# mlx-brd1_091-sensor.net
KiCad netlist of a schematic drawn in Altium Designer
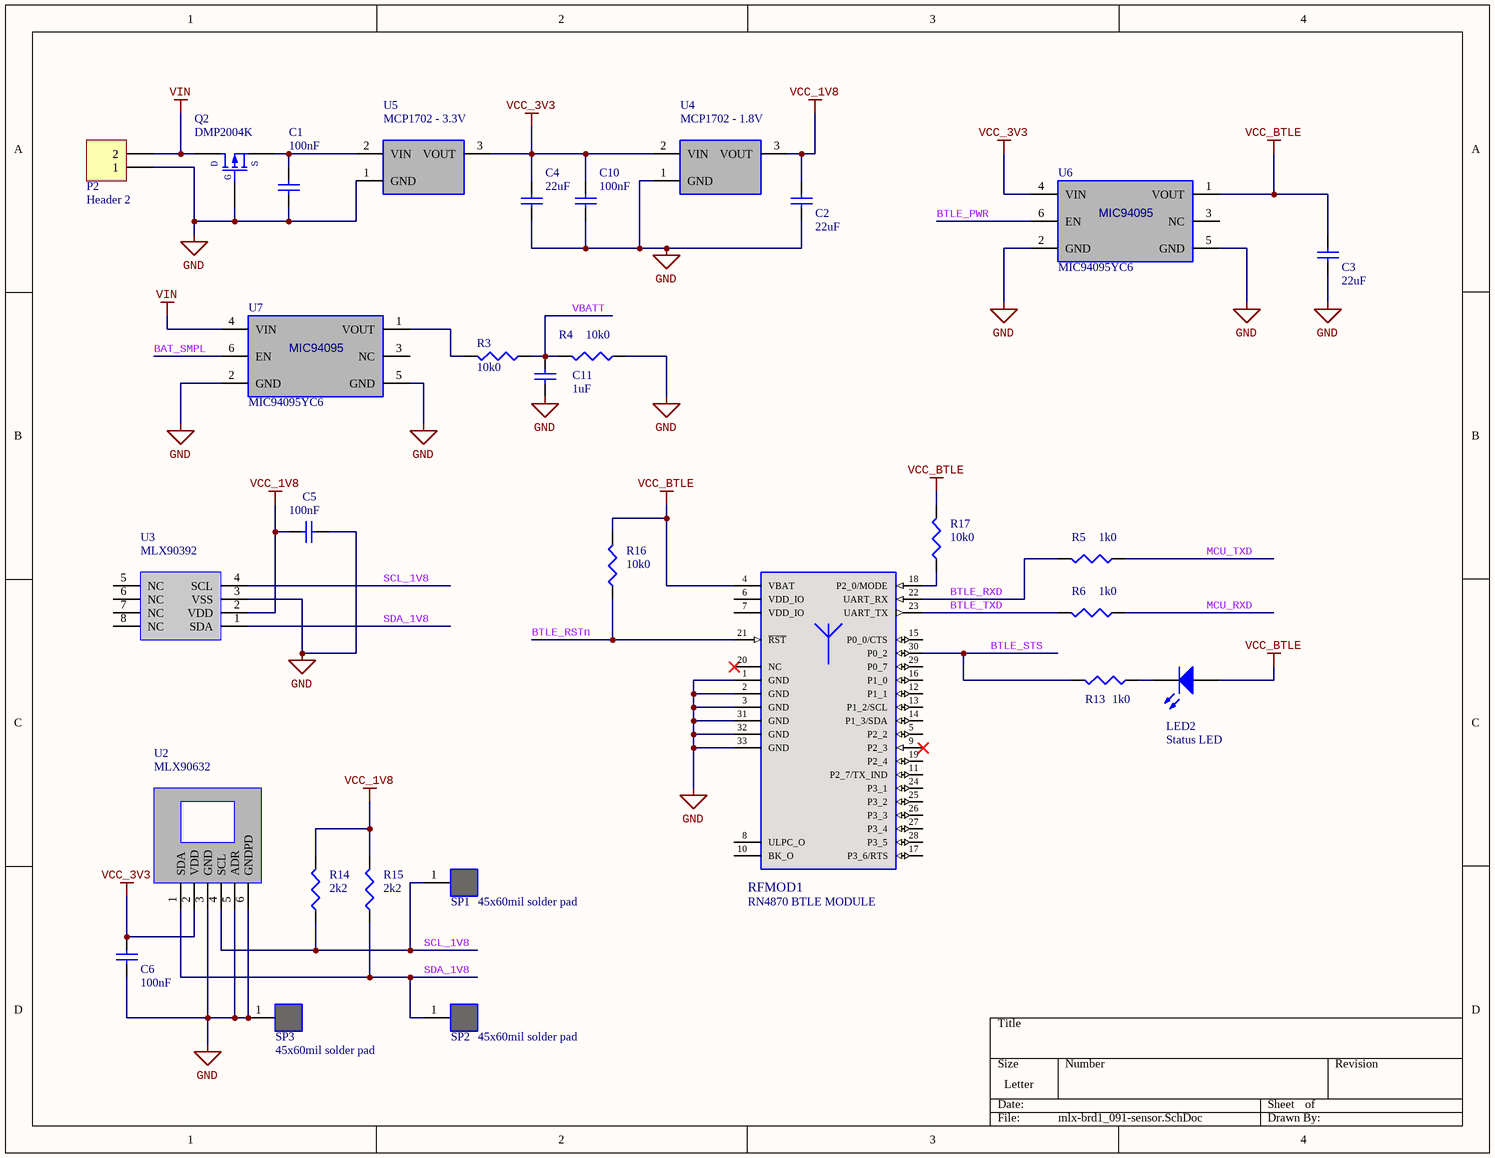
[diagram p0: mlx-brd1_091-sensor.SchDoc]

(export (version "E")
  (design (tool "Eeschema 10.0.6"))
  (components
    (comp (ref "C1")
      (value "100nF")
      (footprint "CAPC1608N")
      (description "Capacitor")
      (fields (field (name "MANUFACTURER") "Yageo") (field (name "MPN") "CC0603KPX7R9BB104"))
      (libsource (lib "Miscellaneous Devices") (part "Cap"))
    )
    (comp (ref "C2")
      (value "22uF")
      (footprint "CAPC3216N")
      (description "Capacitor")
      (fields (field (name "MANUFACTURER") "Yageo") (field (name "MPN") "CC1206MKX5R6BB226"))
      (libsource (lib "Miscellaneous Devices") (part "Cap"))
    )
    (comp (ref "C3")
      (value "22uF")
      (footprint "CAPC3216N")
      (description "Capacitor")
      (fields (field (name "MANUFACTURER") "Yageo") (field (name "MPN") "CC1206MKX5R6BB226"))
      (libsource (lib "Miscellaneous Devices") (part "Cap"))
    )
    (comp (ref "C4")
      (value "22uF")
      (footprint "CAPC3216N")
      (description "Capacitor")
      (fields (field (name "MANUFACTURER") "Yageo") (field (name "MPN") "CC1206MKX5R6BB226"))
      (libsource (lib "Miscellaneous Devices") (part "Cap"))
    )
    (comp (ref "C5")
      (value "100nF")
      (footprint "CAPC1608N")
      (description "Capacitor")
      (fields (field (name "MANUFACTURER") "Yageo") (field (name "MPN") "CC0603KPX7R9BB104"))
      (libsource (lib "Miscellaneous Devices") (part "Cap"))
    )
    (comp (ref "C6")
      (value "100nF")
      (footprint "CAPC1608N")
      (description "Capacitor")
      (fields (field (name "MANUFACTURER") "Yageo") (field (name "MPN") "CC0603KPX7R9BB104"))
      (libsource (lib "Miscellaneous Devices") (part "Cap"))
    )
    (comp (ref "C10")
      (value "100nF")
      (footprint "CAPC1608N")
      (description "Capacitor")
      (fields (field (name "MANUFACTURER") "Yageo") (field (name "MPN") "CC0603KPX7R9BB104"))
      (libsource (lib "Miscellaneous Devices") (part "Cap"))
    )
    (comp (ref "C11")
      (value "1uF")
      (footprint "CAPC1608N")
      (description "Capacitor")
      (fields (field (name "MANUFACTURER") "Taiyo Yuden") (field (name "MPN") "LMK107B7105KA-T"))
      (libsource (lib "Miscellaneous Devices") (part "Cap"))
    )
    (comp (ref "LED2")
      (value "Status LED")
      (footprint "3.2X1.6X1.1")
      (description "Typical RED GaAs LED")
      (fields (field (name "MANUFACTURER") "Inolux") (field (name "MPN") "IN-S126ATA"))
      (libsource (lib "Miscellaneous Devices") (part "LED1"))
    )
    (comp (ref "P2")
      (value "Header 2")
      (footprint "HDR1X2")
      (description "Header, 2-Pin")
      (fields (field (name "MANUFACTURER") "n/a"))
      (libsource (lib "Miscellaneous Connectors") (part "Header 2"))
    )
    (comp (ref "Q2")
      (value "DMP2004K")
      (footprint "SOT23-3N")
      (description "P-Channel MOSFET")
      (fields (field (name "MANUFACTURER") "Diodes Incorporated") (field (name "MPN") "DMP2004K-7"))
      (libsource (lib "melexis_demo") (part "DMP2004K"))
    )
    (comp (ref "R3")
      (value "10k0")
      (footprint "RESC1608N")
      (description "Resistor")
      (fields (field (name "MANUFACTURER") "Stackpole Electronics Inc") (field (name "MPN") "CF18JT10K0"))
      (libsource (lib "Miscellaneous Devices") (part "Res3"))
    )
    (comp (ref "R4")
      (value "10k0")
      (footprint "RESC1608N")
      (description "Resistor")
      (fields (field (name "MANUFACTURER") "Stackpole Electronics Inc") (field (name "MPN") "CF18JT10K0"))
      (libsource (lib "Miscellaneous Devices") (part "Res3"))
    )
    (comp (ref "R5")
      (value "1k0")
      (footprint "RESC1608N")
      (description "Resistor")
      (fields (field (name "MANUFACTURER") "Stackpole Electronics Inc") (field (name "MPN") "CF18JT10K0"))
      (libsource (lib "Miscellaneous Devices") (part "Res3"))
    )
    (comp (ref "R6")
      (value "1k0")
      (footprint "RESC1608N")
      (description "Resistor")
      (fields (field (name "MANUFACTURER") "Stackpole Electronics Inc") (field (name "MPN") "CF18JT10K0"))
      (libsource (lib "Miscellaneous Devices") (part "Res3"))
    )
    (comp (ref "R13")
      (value "1k0")
      (footprint "RESC1608N")
      (description "Resistor")
      (fields (field (name "MANUFACTURER") "Stackpole Electronics Inc") (field (name "MPN") "CF18JT10K0"))
      (libsource (lib "Miscellaneous Devices") (part "Res3"))
    )
    (comp (ref "R14")
      (value "2k2")
      (footprint "RESC1608N")
      (description "Resistor")
      (fields (field (name "MANUFACTURER") "Stackpole Electronics Inc") (field (name "MPN") "CF18JT10K0"))
      (libsource (lib "Miscellaneous Devices") (part "Res3"))
    )
    (comp (ref "R15")
      (value "2k2")
      (footprint "RESC1608N")
      (description "Resistor")
      (fields (field (name "MANUFACTURER") "Stackpole Electronics Inc") (field (name "MPN") "CF18JT10K0"))
      (libsource (lib "Miscellaneous Devices") (part "Res3"))
    )
    (comp (ref "R16")
      (value "10k0")
      (footprint "RESC1608N")
      (description "Resistor")
      (fields (field (name "MANUFACTURER") "Stackpole Electronics Inc") (field (name "MPN") "CF18JT10K0"))
      (libsource (lib "Miscellaneous Devices") (part "Res3"))
    )
    (comp (ref "R17")
      (value "10k0")
      (footprint "RESC1608N")
      (description "Resistor")
      (fields (field (name "MANUFACTURER") "Stackpole Electronics Inc") (field (name "MPN") "CF18JT10K0"))
      (libsource (lib "Miscellaneous Devices") (part "Res3"))
    )
    (comp (ref "RFMOD1")
      (value "RN4870 BTLE MODULE")
      (footprint "AP6-00539")
      (description "Bluetooth LE Module")
      (fields (field (name "MANUFACTURER") "Microchip Technology") (field (name "MPN") "RN4870-V/RM140"))
      (libsource (lib "melexis_demo") (part "RN4870-V"))
    )
    (comp (ref "SP1")
      (value "45x60mil solder pad")
      (footprint "sp45x60")
      (libsource (lib "mlx-brd1") (part "sp45x60"))
    )
    (comp (ref "SP2")
      (value "45x60mil solder pad")
      (footprint "sp45x60")
      (libsource (lib "mlx-brd1") (part "sp45x60"))
    )
    (comp (ref "SP3")
      (value "45x60mil solder pad")
      (footprint "sp45x60")
      (libsource (lib "mlx-brd1") (part "sp45x60"))
    )
    (comp (ref "U2")
      (value "MLX90632")
      (footprint "MLX90632_FIR_M2")
      (fields (field (name "MANUFACTURER") "Melexis") (field (name "MPN") "MLX90632-S-LD-DCB-100"))
      (libsource (lib "melexis_demo") (part "MLX90632-FIR"))
    )
    (comp (ref "U3")
      (value "MLX90392")
      (footprint "UTDFN8_2.5x2x0.4V2")
      (fields (field (name "MANUFACTURER") "Melexis") (field (name "MPN") "MLX90392ELQ-AAA-010-RE"))
      (libsource (lib "melexis_demo") (part "MLX90392-mag"))
    )
    (comp (ref "U4")
      (value "MCP1702 - 1.8V")
      (footprint "MC1702-TO92")
      (fields (field (name "MANUFACTURER") "Microchip Technology") (field (name "MPN") "MCP1702-3302E/TO"))
      (libsource (lib "melexis_demo") (part "MCP1702-TO92"))
    )
    (comp (ref "U5")
      (value "MCP1702 - 3.3V")
      (footprint "MC1702-TO92")
      (fields (field (name "MANUFACTURER") "Microchip Technology") (field (name "MPN") "MCP1702-1802E/TO"))
      (libsource (lib "melexis_demo") (part "MCP1702-TO92"))
    )
    (comp (ref "U6")
      (value "MIC94095YC6")
      (footprint "SC-70")
      (fields (field (name "MANUFACTURER") "Microchip Technology") (field (name "MPN") "MIC94095YC6-TR"))
      (libsource (lib "mlx-brd1") (part "MIC94095YC6"))
    )
    (comp (ref "U7")
      (value "MIC94095YC6")
      (footprint "SC-70")
      (fields (field (name "MANUFACTURER") "Microchip Technology") (field (name "MPN") "MIC94095YC6-TR"))
      (libsource (lib "mlx-brd1") (part "MIC94095YC6"))
    )
  )
  (nets
    (net (code "1") (name "/BAT_SMPL") (class "Default")
      (node (ref "U7") (pin "6") (pinfunction "EN_6") (pintype "passive"))
    )
    (net (code "2") (name "/BTLE_PWR") (class "Default")
      (node (ref "U6") (pin "6") (pinfunction "EN_6") (pintype "passive"))
    )
    (net (code "3") (name "/BTLE_RSTn") (class "Default")
      (node (ref "R16") (pin "1") (pinfunction "1_1") (pintype "passive"))
      (node (ref "RFMOD1") (pin "21") (pinfunction "~{RST}_21") (pintype "input"))
    )
    (net (code "4") (name "/BTLE_RXD") (class "Default")
      (node (ref "R5") (pin "2") (pinfunction "2_2") (pintype "passive"))
      (node (ref "RFMOD1") (pin "22") (pinfunction "UART_RX_22") (pintype "input"))
    )
    (net (code "5") (name "/BTLE_STS") (class "Default")
      (node (ref "R13") (pin "2") (pinfunction "2_2") (pintype "passive"))
      (node (ref "RFMOD1") (pin "30") (pinfunction "P0_2_30") (pintype "bidirectional"))
    )
    (net (code "6") (name "/BTLE_TXD") (class "Default")
      (node (ref "R6") (pin "2") (pinfunction "2_2") (pintype "passive"))
      (node (ref "RFMOD1") (pin "23") (pinfunction "UART_TX_23") (pintype "output"))
    )
    (net (code "7") (name "/MCU_RXD") (class "Default")
      (node (ref "R6") (pin "1") (pinfunction "1_1") (pintype "passive"))
    )
    (net (code "8") (name "/MCU_TXD") (class "Default")
      (node (ref "R5") (pin "1") (pinfunction "1_1") (pintype "passive"))
    )
    (net (code "9") (name "/SCL_1V8") (class "Default")
      (node (ref "R14") (pin "1") (pinfunction "1_1") (pintype "passive"))
      (node (ref "SP1") (pin "1") (pinfunction "1_1") (pintype "passive"))
      (node (ref "U2") (pin "4") (pinfunction "SCL_4") (pintype "passive"))
      (node (ref "U3") (pin "4") (pinfunction "SCL_4") (pintype "passive"))
    )
    (net (code "10") (name "/SDA_1V8") (class "Default")
      (node (ref "R15") (pin "1") (pinfunction "1_1") (pintype "passive"))
      (node (ref "SP2") (pin "1") (pinfunction "1_1") (pintype "passive"))
      (node (ref "U2") (pin "1") (pinfunction "SDA_1") (pintype "passive"))
      (node (ref "U3") (pin "1") (pinfunction "SDA_1") (pintype "passive"))
    )
    (net (code "11") (name "/VBATT") (class "Default")
      (node (ref "C11") (pin "2") (pinfunction "2_2") (pintype "passive"))
      (node (ref "R3") (pin "1") (pinfunction "1_1") (pintype "passive"))
      (node (ref "R4") (pin "2") (pinfunction "2_2") (pintype "passive"))
    )
    (net (code "12") (name "GND") (class "Default")
      (node (ref "C1") (pin "1") (pinfunction "1_1") (pintype "passive"))
      (node (ref "C10") (pin "1") (pinfunction "1_1") (pintype "passive"))
      (node (ref "C11") (pin "1") (pinfunction "1_1") (pintype "passive"))
      (node (ref "C2") (pin "1") (pinfunction "1_1") (pintype "passive"))
      (node (ref "C3") (pin "1") (pinfunction "1_1") (pintype "passive"))
      (node (ref "C4") (pin "1") (pinfunction "1_1") (pintype "passive"))
      (node (ref "C5") (pin "1") (pinfunction "1_1") (pintype "passive"))
      (node (ref "C6") (pin "1") (pinfunction "1_1") (pintype "passive"))
      (node (ref "P2") (pin "1") (pinfunction "1_1") (pintype "passive"))
      (node (ref "Q2") (pin "1") (pinfunction "G_1") (pintype "passive"))
      (node (ref "R4") (pin "1") (pinfunction "1_1") (pintype "passive"))
      (node (ref "RFMOD1") (pin "1") (pinfunction "GND_1") (pintype "power_in"))
      (node (ref "RFMOD1") (pin "2") (pinfunction "GND_2") (pintype "power_in"))
      (node (ref "RFMOD1") (pin "3") (pinfunction "GND_3") (pintype "power_in"))
      (node (ref "RFMOD1") (pin "31") (pinfunction "GND_31") (pintype "power_in"))
      (node (ref "RFMOD1") (pin "32") (pinfunction "GND_32") (pintype "power_in"))
      (node (ref "RFMOD1") (pin "33") (pinfunction "GND_33") (pintype "power_in"))
      (node (ref "SP3") (pin "1") (pinfunction "1_1") (pintype "passive"))
      (node (ref "U2") (pin "3") (pinfunction "GND_3") (pintype "passive"))
      (node (ref "U2") (pin "5") (pinfunction "ADR_5") (pintype "passive"))
      (node (ref "U2") (pin "6") (pinfunction "GNDPD_6") (pintype "passive"))
      (node (ref "U3") (pin "3") (pinfunction "VSS_3") (pintype "passive"))
      (node (ref "U4") (pin "1") (pinfunction "GND_1") (pintype "passive"))
      (node (ref "U5") (pin "1") (pinfunction "GND_1") (pintype "passive"))
      (node (ref "U6") (pin "2") (pinfunction "GND_2") (pintype "passive"))
      (node (ref "U6") (pin "5") (pinfunction "GND_5") (pintype "passive"))
      (node (ref "U7") (pin "2") (pinfunction "GND_2") (pintype "passive"))
      (node (ref "U7") (pin "5") (pinfunction "GND_5") (pintype "passive"))
    )
    (net (code "13") (name "Net-(LED2-K)") (class "Default")
      (node (ref "LED2") (pin "2") (pinfunction "K_2") (pintype "passive"))
      (node (ref "R13") (pin "1") (pinfunction "1_1") (pintype "passive"))
    )
    (net (code "14") (name "Net-(Q2-S)") (class "Default")
      (node (ref "C1") (pin "2") (pinfunction "2_2") (pintype "passive"))
      (node (ref "Q2") (pin "2") (pinfunction "S_2") (pintype "passive"))
      (node (ref "U5") (pin "2") (pinfunction "VIN_2") (pintype "passive"))
    )
    (net (code "15") (name "Net-(RFMOD1-P2_0{slash}MODE)") (class "Default")
      (node (ref "R17") (pin "1") (pinfunction "1_1") (pintype "passive"))
      (node (ref "RFMOD1") (pin "18") (pinfunction "P2_0/MODE_18") (pintype "input"))
    )
    (net (code "16") (name "Net-(U7-VOUT)") (class "Default")
      (node (ref "R3") (pin "2") (pinfunction "2_2") (pintype "passive"))
      (node (ref "U7") (pin "1") (pinfunction "VOUT_1") (pintype "passive"))
    )
    (net (code "17") (name "VCC_1V8") (class "Default")
      (node (ref "C2") (pin "2") (pinfunction "2_2") (pintype "passive"))
      (node (ref "C5") (pin "2") (pinfunction "2_2") (pintype "passive"))
      (node (ref "R14") (pin "2") (pinfunction "2_2") (pintype "passive"))
      (node (ref "R15") (pin "2") (pinfunction "2_2") (pintype "passive"))
      (node (ref "U3") (pin "2") (pinfunction "VDD_2") (pintype "passive"))
      (node (ref "U4") (pin "3") (pinfunction "VOUT_3") (pintype "passive"))
    )
    (net (code "18") (name "VCC_3V3") (class "Default")
      (node (ref "C10") (pin "2") (pinfunction "2_2") (pintype "passive"))
      (node (ref "C4") (pin "2") (pinfunction "2_2") (pintype "passive"))
      (node (ref "C6") (pin "2") (pinfunction "2_2") (pintype "passive"))
      (node (ref "U2") (pin "2") (pinfunction "VDD_2") (pintype "passive"))
      (node (ref "U4") (pin "2") (pinfunction "VIN_2") (pintype "passive"))
      (node (ref "U5") (pin "3") (pinfunction "VOUT_3") (pintype "passive"))
      (node (ref "U6") (pin "4") (pinfunction "VIN_4") (pintype "passive"))
    )
    (net (code "19") (name "VCC_BTLE") (class "Default")
      (node (ref "C3") (pin "2") (pinfunction "2_2") (pintype "passive"))
      (node (ref "LED2") (pin "1") (pinfunction "A_1") (pintype "passive"))
      (node (ref "R16") (pin "2") (pinfunction "2_2") (pintype "passive"))
      (node (ref "R17") (pin "2") (pinfunction "2_2") (pintype "passive"))
      (node (ref "RFMOD1") (pin "4") (pinfunction "VBAT_4") (pintype "power_in"))
      (node (ref "U6") (pin "1") (pinfunction "VOUT_1") (pintype "passive"))
    )
    (net (code "20") (name "VIN") (class "Default")
      (node (ref "P2") (pin "2") (pinfunction "2_2") (pintype "passive"))
      (node (ref "Q2") (pin "3") (pinfunction "D_3") (pintype "passive"))
      (node (ref "U7") (pin "4") (pinfunction "VIN_4") (pintype "passive"))
    )
    (net (code "21") (name "unconnected-(RFMOD1-BK_O-Pad10)") (class "Default")
      (node (ref "RFMOD1") (pin "10") (pinfunction "BK_O_10") (pintype "passive"))
    )
    (net (code "22") (name "unconnected-(RFMOD1-NC-Pad20)") (class "Default")
      (node (ref "RFMOD1") (pin "20") (pinfunction "NC_20") (pintype "passive+no_connect"))
    )
    (net (code "23") (name "unconnected-(RFMOD1-P0_0{slash}CTS-Pad15)") (class "Default")
      (node (ref "RFMOD1") (pin "15") (pinfunction "P0_0/CTS_15") (pintype "bidirectional"))
    )
    (net (code "24") (name "unconnected-(RFMOD1-P0_7-Pad29)") (class "Default")
      (node (ref "RFMOD1") (pin "29") (pinfunction "P0_7_29") (pintype "bidirectional"))
    )
    (net (code "25") (name "unconnected-(RFMOD1-P1_0-Pad16)") (class "Default")
      (node (ref "RFMOD1") (pin "16") (pinfunction "P1_0_16") (pintype "bidirectional"))
    )
    (net (code "26") (name "unconnected-(RFMOD1-P1_1-Pad12)") (class "Default")
      (node (ref "RFMOD1") (pin "12") (pinfunction "P1_1_12") (pintype "bidirectional"))
    )
    (net (code "27") (name "unconnected-(RFMOD1-P1_2{slash}SCL-Pad13)") (class "Default")
      (node (ref "RFMOD1") (pin "13") (pinfunction "P1_2/SCL_13") (pintype "bidirectional"))
    )
    (net (code "28") (name "unconnected-(RFMOD1-P1_3{slash}SDA-Pad14)") (class "Default")
      (node (ref "RFMOD1") (pin "14") (pinfunction "P1_3/SDA_14") (pintype "bidirectional"))
    )
    (net (code "29") (name "unconnected-(RFMOD1-P2_2-Pad5)") (class "Default")
      (node (ref "RFMOD1") (pin "5") (pinfunction "P2_2_5") (pintype "bidirectional"))
    )
    (net (code "30") (name "unconnected-(RFMOD1-P2_3-Pad9)") (class "Default")
      (node (ref "RFMOD1") (pin "9") (pinfunction "P2_3_9") (pintype "input+no_connect"))
    )
    (net (code "31") (name "unconnected-(RFMOD1-P2_4-Pad19)") (class "Default")
      (node (ref "RFMOD1") (pin "19") (pinfunction "P2_4_19") (pintype "bidirectional"))
    )
    (net (code "32") (name "unconnected-(RFMOD1-P2_7{slash}TX_IND-Pad11)") (class "Default")
      (node (ref "RFMOD1") (pin "11") (pinfunction "P2_7/TX_IND_11") (pintype "bidirectional"))
    )
    (net (code "33") (name "unconnected-(RFMOD1-P3_1-Pad24)") (class "Default")
      (node (ref "RFMOD1") (pin "24") (pinfunction "P3_1_24") (pintype "bidirectional"))
    )
    (net (code "34") (name "unconnected-(RFMOD1-P3_2-Pad25)") (class "Default")
      (node (ref "RFMOD1") (pin "25") (pinfunction "P3_2_25") (pintype "bidirectional"))
    )
    (net (code "35") (name "unconnected-(RFMOD1-P3_3-Pad26)") (class "Default")
      (node (ref "RFMOD1") (pin "26") (pinfunction "P3_3_26") (pintype "bidirectional"))
    )
    (net (code "36") (name "unconnected-(RFMOD1-P3_4-Pad27)") (class "Default")
      (node (ref "RFMOD1") (pin "27") (pinfunction "P3_4_27") (pintype "bidirectional"))
    )
    (net (code "37") (name "unconnected-(RFMOD1-P3_5-Pad28)") (class "Default")
      (node (ref "RFMOD1") (pin "28") (pinfunction "P3_5_28") (pintype "bidirectional"))
    )
    (net (code "38") (name "unconnected-(RFMOD1-P3_6{slash}RTS-Pad17)") (class "Default")
      (node (ref "RFMOD1") (pin "17") (pinfunction "P3_6/RTS_17") (pintype "bidirectional"))
    )
    (net (code "39") (name "unconnected-(RFMOD1-ULPC_O-Pad8)") (class "Default")
      (node (ref "RFMOD1") (pin "8") (pinfunction "ULPC_O_8") (pintype "passive"))
    )
    (net (code "40") (name "unconnected-(RFMOD1-VDD_IO-Pad6)") (class "Default")
      (node (ref "RFMOD1") (pin "6") (pinfunction "VDD_IO_6") (pintype "power_in"))
    )
    (net (code "41") (name "unconnected-(RFMOD1-VDD_IO-Pad7)") (class "Default")
      (node (ref "RFMOD1") (pin "7") (pinfunction "VDD_IO_7") (pintype "power_in"))
    )
    (net (code "42") (name "unconnected-(U3-NC-Pad5)") (class "Default")
      (node (ref "U3") (pin "5") (pinfunction "NC_5") (pintype "passive"))
    )
    (net (code "43") (name "unconnected-(U3-NC-Pad6)") (class "Default")
      (node (ref "U3") (pin "6") (pinfunction "NC_6") (pintype "passive"))
    )
    (net (code "44") (name "unconnected-(U3-NC-Pad7)") (class "Default")
      (node (ref "U3") (pin "7") (pinfunction "NC_7") (pintype "passive"))
    )
    (net (code "45") (name "unconnected-(U3-NC-Pad8)") (class "Default")
      (node (ref "U3") (pin "8") (pinfunction "NC_8") (pintype "passive"))
    )
    (net (code "46") (name "unconnected-(U6-NC-Pad3)") (class "Default")
      (node (ref "U6") (pin "3") (pinfunction "NC_3") (pintype "passive"))
    )
    (net (code "47") (name "unconnected-(U7-NC-Pad3)") (class "Default")
      (node (ref "U7") (pin "3") (pinfunction "NC_3") (pintype "passive"))
    )
  )
)
